# openservo.net
KiCad netlist of a schematic drawn in Altium Designer
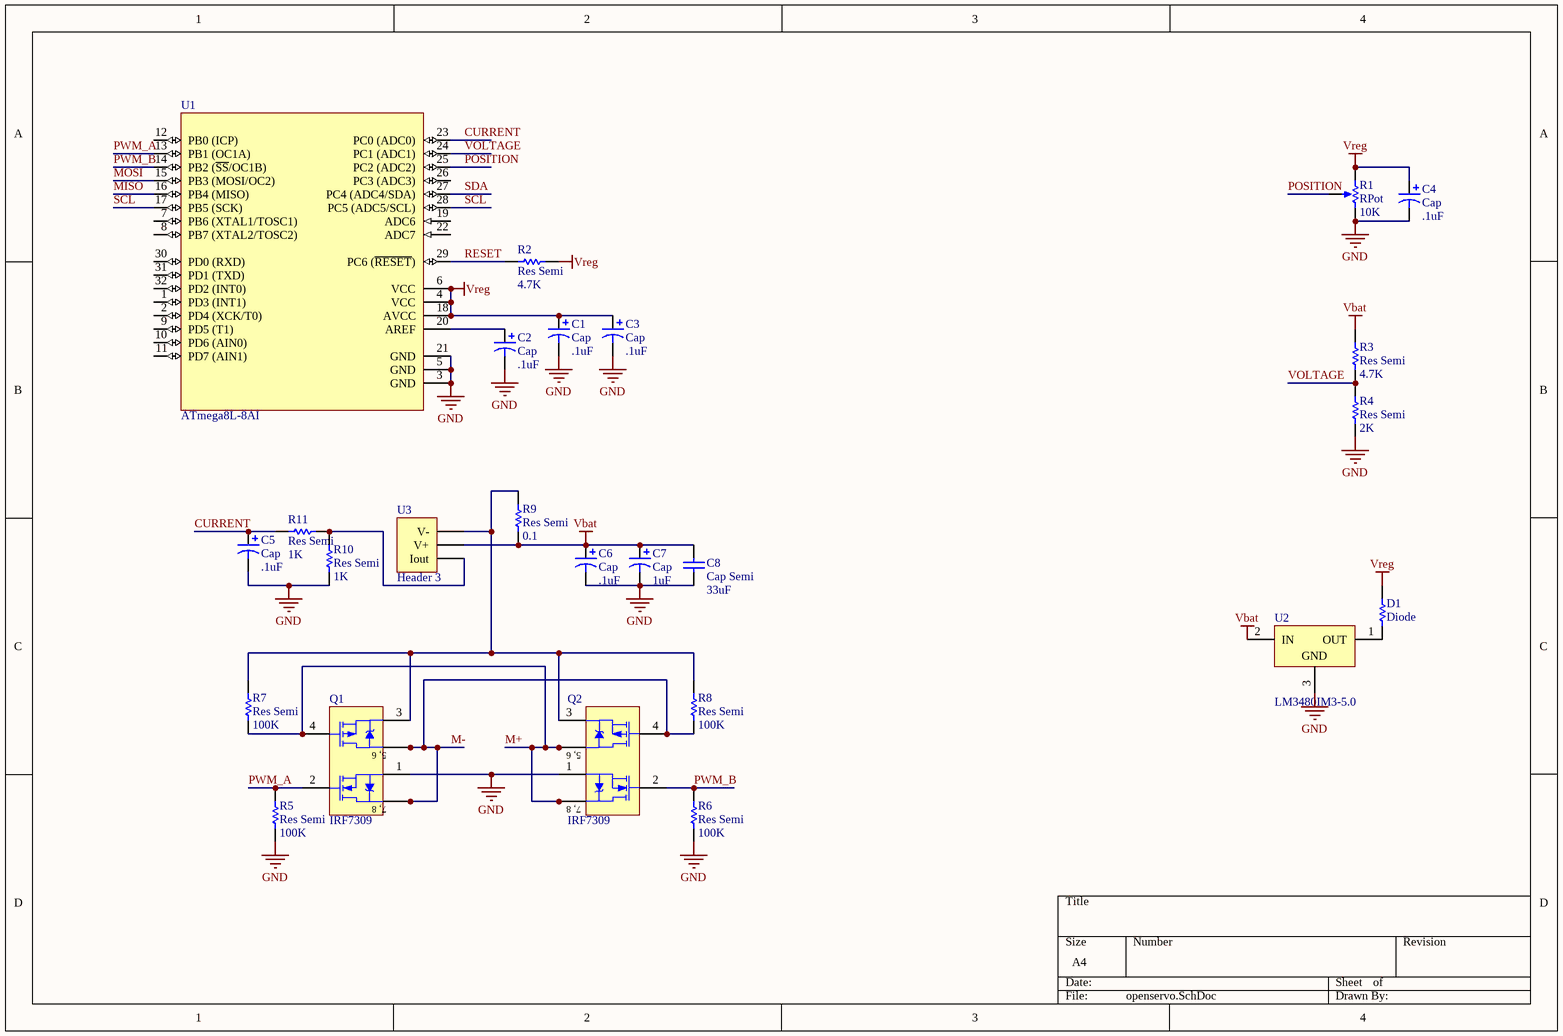
[diagram p0: openservo.SchDoc]

(export (version "E")
  (design (tool "Eeschema 10.0.6"))
  (components
    (comp (ref "C1")
      (value "Cap")
      (footprint "J1-0603")
      (description "Polarized Capacitor (Surface Mount)")
      (fields (field (name "ALTIUM_VALUE") ".1uF") (field (name "PUBLISHER") "Altium Limited"))
      (libsource (lib "Miscellaneous Devices") (part "Cap Semi"))
    )
    (comp (ref "C2")
      (value "Cap")
      (footprint "J1-0603")
      (description "Polarized Capacitor (Surface Mount)")
      (fields (field (name "ALTIUM_VALUE") ".1uF") (field (name "PUBLISHER") "Altium Limited"))
      (libsource (lib "Miscellaneous Devices") (part "Cap Semi"))
    )
    (comp (ref "C3")
      (value "Cap")
      (footprint "J1-0603")
      (description "Polarized Capacitor (Surface Mount)")
      (fields (field (name "ALTIUM_VALUE") ".1uF") (field (name "PUBLISHER") "Altium Limited"))
      (libsource (lib "Miscellaneous Devices") (part "Cap Semi"))
    )
    (comp (ref "C4")
      (value "Cap")
      (footprint "J1-0603")
      (description "Polarized Capacitor (Surface Mount)")
      (fields (field (name "ALTIUM_VALUE") ".1uF") (field (name "PUBLISHER") "Altium Limited"))
      (libsource (lib "Miscellaneous Devices") (part "Cap Semi"))
    )
    (comp (ref "C5")
      (value "Cap")
      (footprint "J1-0603")
      (description "Polarized Capacitor (Surface Mount)")
      (fields (field (name "ALTIUM_VALUE") ".1uF") (field (name "PUBLISHER") "Altium Limited"))
      (libsource (lib "Miscellaneous Devices") (part "Cap Semi"))
    )
    (comp (ref "C6")
      (value "Cap")
      (footprint "J1-0603")
      (description "Polarized Capacitor (Surface Mount)")
      (fields (field (name "ALTIUM_VALUE") ".1uF") (field (name "PUBLISHER") "Altium Limited"))
      (libsource (lib "Miscellaneous Devices") (part "Cap Semi"))
    )
    (comp (ref "C7")
      (value "Cap")
      (footprint "J1-0603")
      (description "Polarized Capacitor (Surface Mount)")
      (fields (field (name "ALTIUM_VALUE") "1uF") (field (name "PUBLISHER") "Altium Limited"))
      (libsource (lib "Miscellaneous Devices") (part "Cap Semi"))
    )
    (comp (ref "C8")
      (value "Cap Semi")
      (footprint "C1210")
      (description "Capacitor (Semiconductor SIM Model)")
      (fields (field (name "ALTIUM_VALUE") "33uF") (field (name "PUBLISHER") "Altium Limited"))
      (libsource (lib "") (part "Cap Semi_1"))
    )
    (comp (ref "D1")
      (value "Diode")
      (footprint "2012[0805]")
      (description "Semiconductor Resistor")
      (fields (field (name "PUBLISHER") "Altium Limited"))
      (libsource (lib "Miscellaneous Devices") (part "Res Semi"))
    )
    (comp (ref "Q1")
      (value "IRF7309")
      (footprint "SO-8_N")
      (description "HEXFET Power MOSFET")
      (fields (field (name "PUBLISHER") "Altium Limited"))
      (libsource (lib "IR Discrete MOSFET - Power") (part "IRF7309"))
    )
    (comp (ref "Q2")
      (value "IRF7309")
      (footprint "SO-8_N")
      (description "HEXFET Power MOSFET")
      (fields (field (name "PUBLISHER") "Altium Limited"))
      (libsource (lib "") (part "IRF7309_1"))
    )
    (comp (ref "R1")
      (value "RPot")
      (footprint "VR5")
      (description "Potentiometer")
      (fields (field (name "ALTIUM_VALUE") "10K") (field (name "PUBLISHER") "Altium Limited"))
      (libsource (lib "Miscellaneous Devices") (part "RPot"))
    )
    (comp (ref "R2")
      (value "Res Semi")
      (footprint "1608[0603]")
      (description "Semiconductor Resistor")
      (fields (field (name "ALTIUM_VALUE") "4.7K") (field (name "PUBLISHER") "Altium Limited"))
      (libsource (lib "Miscellaneous Devices") (part "Res Semi"))
    )
    (comp (ref "R3")
      (value "Res Semi")
      (footprint "1608[0603]")
      (description "Semiconductor Resistor")
      (fields (field (name "ALTIUM_VALUE") "4.7K") (field (name "PUBLISHER") "Altium Limited"))
      (libsource (lib "Miscellaneous Devices") (part "Res Semi"))
    )
    (comp (ref "R4")
      (value "Res Semi")
      (footprint "1608[0603]")
      (description "Semiconductor Resistor")
      (fields (field (name "ALTIUM_VALUE") "2K") (field (name "PUBLISHER") "Altium Limited"))
      (libsource (lib "Miscellaneous Devices") (part "Res Semi"))
    )
    (comp (ref "R5")
      (value "Res Semi")
      (footprint "1608[0603]")
      (description "Semiconductor Resistor")
      (fields (field (name "ALTIUM_VALUE") "100K") (field (name "PUBLISHER") "Altium Limited"))
      (libsource (lib "Miscellaneous Devices") (part "Res Semi"))
    )
    (comp (ref "R6")
      (value "Res Semi")
      (footprint "1608[0603]")
      (description "Semiconductor Resistor")
      (fields (field (name "ALTIUM_VALUE") "100K") (field (name "PUBLISHER") "Altium Limited"))
      (libsource (lib "Miscellaneous Devices") (part "Res Semi"))
    )
    (comp (ref "R7")
      (value "Res Semi")
      (footprint "1608[0603]")
      (description "Semiconductor Resistor")
      (fields (field (name "ALTIUM_VALUE") "100K") (field (name "PUBLISHER") "Altium Limited"))
      (libsource (lib "Miscellaneous Devices") (part "Res Semi"))
    )
    (comp (ref "R8")
      (value "Res Semi")
      (footprint "1608[0603]")
      (description "Semiconductor Resistor")
      (fields (field (name "ALTIUM_VALUE") "100K") (field (name "PUBLISHER") "Altium Limited"))
      (libsource (lib "Miscellaneous Devices") (part "Res Semi"))
    )
    (comp (ref "R9")
      (value "Res Semi")
      (footprint "3216[1206]")
      (description "Semiconductor Resistor")
      (fields (field (name "ALTIUM_VALUE") "0.1") (field (name "PUBLISHER") "Altium Limited"))
      (libsource (lib "Miscellaneous Devices") (part "Res Semi"))
    )
    (comp (ref "R10")
      (value "Res Semi")
      (footprint "1608[0603]")
      (description "Semiconductor Resistor")
      (fields (field (name "ALTIUM_VALUE") "1K") (field (name "PUBLISHER") "Altium Limited"))
      (libsource (lib "Miscellaneous Devices") (part "Res Semi"))
    )
    (comp (ref "R11")
      (value "Res Semi")
      (footprint "1608[0603]")
      (description "Semiconductor Resistor")
      (fields (field (name "ALTIUM_VALUE") "1K") (field (name "PUBLISHER") "Altium Limited"))
      (libsource (lib "Miscellaneous Devices") (part "Res Semi"))
    )
    (comp (ref "U1")
      (value "ATmega8L-8AI")
      (footprint "32A_N")
      (description "8-Bit AVR Microcontroller with 8K Bytes of In-System Programmable Flash Memory")
      (fields (field (name "PUBLISHER") "Altium Limited"))
      (libsource (lib "Atmel Microcontroller 8-Bit AVR") (part "ATmega8L-8AI"))
    )
    (comp (ref "U2")
      (value "LM3480IM3-5.0")
      (footprint "MF03A_N")
      (description "100 mA, SOT-23, Quasi Low-Dropout Linear Voltage Regulator")
      (fields
        (field (name "MANUFACTURER") "National Semiconductor")
        (field (name "DIGIKEYPARTNUMBER") "LM3480IM3-5.0CT-ND")
        (field (name "PUBLISHER") "Altium Limited")
      )
      (libsource (lib "NSC LDO") (part "LM3480IM3-5.0"))
    )
    (comp (ref "U3")
      (value "Header 3")
      (footprint "Philips Discrete BJT - Darlington:SOT23_L")
      (description "Header, 3-Pin")
      (fields (field (name "PUBLISHER") "Altium Limited"))
      (libsource (lib "Miscellaneous Connectors") (part "Header 3"))
    )
  )
  (nets
    (net (code "1") (name "/CURRENT") (class "Default")
      (node (ref "C5") (pin "1") (pinfunction "1_1") (pintype "passive"))
      (node (ref "R11") (pin "2") (pinfunction "2_2") (pintype "passive"))
      (node (ref "U1") (pin "23") (pinfunction "PC0_(ADC0)_23") (pintype "bidirectional"))
    )
    (net (code "2") (name "/M+") (class "Default")
      (node (ref "Q1") (pin "4") (pinfunction "G2_4") (pintype "passive"))
      (node (ref "Q2") (pin "5") (pinfunction "D2_5") (pintype "passive"))
      (node (ref "Q2") (pin "6") (pinfunction "D2_6") (pintype "passive"))
      (node (ref "Q2") (pin "7") (pinfunction "D1_7") (pintype "passive"))
      (node (ref "Q2") (pin "8") (pinfunction "D1_8") (pintype "passive"))
      (node (ref "R7") (pin "1") (pinfunction "1_1") (pintype "passive"))
    )
    (net (code "3") (name "/M-") (class "Default")
      (node (ref "Q1") (pin "5") (pinfunction "D2_5") (pintype "passive"))
      (node (ref "Q1") (pin "6") (pinfunction "D2_6") (pintype "passive"))
      (node (ref "Q1") (pin "7") (pinfunction "D1_7") (pintype "passive"))
      (node (ref "Q1") (pin "8") (pinfunction "D1_8") (pintype "passive"))
      (node (ref "Q2") (pin "4") (pinfunction "G2_4") (pintype "passive"))
      (node (ref "R8") (pin "1") (pinfunction "1_1") (pintype "passive"))
    )
    (net (code "4") (name "/MISO") (class "Default")
      (node (ref "U1") (pin "16") (pinfunction "PB4_(MISO)_16") (pintype "bidirectional"))
    )
    (net (code "5") (name "/MOSI") (class "Default")
      (node (ref "U1") (pin "15") (pinfunction "PB3_(MOSI/OC2)_15") (pintype "bidirectional"))
    )
    (net (code "6") (name "/POSITION") (class "Default")
      (node (ref "R1") (pin "2") (pinfunction "TAP_2") (pintype "passive"))
      (node (ref "U1") (pin "25") (pinfunction "PC2_(ADC2)_25") (pintype "bidirectional"))
    )
    (net (code "7") (name "/PWM_A") (class "Default")
      (node (ref "Q1") (pin "2") (pinfunction "G1_2") (pintype "passive"))
      (node (ref "R5") (pin "2") (pinfunction "2_2") (pintype "passive"))
      (node (ref "U1") (pin "13") (pinfunction "PB1_(OC1A)_13") (pintype "bidirectional"))
    )
    (net (code "8") (name "/PWM_B") (class "Default")
      (node (ref "Q2") (pin "2") (pinfunction "G1_2") (pintype "passive"))
      (node (ref "R6") (pin "2") (pinfunction "2_2") (pintype "passive"))
      (node (ref "U1") (pin "14") (pinfunction "PB2_(~{SS}/OC1B)_14") (pintype "bidirectional"))
    )
    (net (code "9") (name "/RESET") (class "Default")
      (node (ref "R2") (pin "1") (pinfunction "1_1") (pintype "passive"))
      (node (ref "U1") (pin "29") (pinfunction "PC6_(~{RESET})_29") (pintype "bidirectional"))
    )
    (net (code "10") (name "/SCL") (class "Default")
      (node (ref "U1") (pin "17") (pinfunction "PB5_(SCK)_17") (pintype "bidirectional"))
      (node (ref "U1") (pin "28") (pinfunction "PC5_(ADC5/SCL)_28") (pintype "bidirectional"))
    )
    (net (code "11") (name "/SDA") (class "Default")
      (node (ref "U1") (pin "27") (pinfunction "PC4_(ADC4/SDA)_27") (pintype "bidirectional"))
    )
    (net (code "12") (name "/VOLTAGE") (class "Default")
      (node (ref "R3") (pin "1") (pinfunction "1_1") (pintype "passive"))
      (node (ref "R4") (pin "2") (pinfunction "2_2") (pintype "passive"))
      (node (ref "U1") (pin "24") (pinfunction "PC1_(ADC1)_24") (pintype "bidirectional"))
    )
    (net (code "13") (name "GND") (class "Default")
      (node (ref "C1") (pin "2") (pinfunction "2_2") (pintype "passive"))
      (node (ref "C2") (pin "2") (pinfunction "2_2") (pintype "passive"))
      (node (ref "C3") (pin "2") (pinfunction "2_2") (pintype "passive"))
      (node (ref "C4") (pin "2") (pinfunction "2_2") (pintype "passive"))
      (node (ref "C5") (pin "2") (pinfunction "2_2") (pintype "passive"))
      (node (ref "C6") (pin "2") (pinfunction "2_2") (pintype "passive"))
      (node (ref "C7") (pin "2") (pinfunction "2_2") (pintype "passive"))
      (node (ref "C8") (pin "1") (pinfunction "1_1") (pintype "passive"))
      (node (ref "Q1") (pin "1") (pinfunction "S1_1") (pintype "passive"))
      (node (ref "Q2") (pin "1") (pinfunction "S1_1") (pintype "passive"))
      (node (ref "R1") (pin "3") (pinfunction "BOT_3") (pintype "passive"))
      (node (ref "R10") (pin "1") (pinfunction "1_1") (pintype "passive"))
      (node (ref "R4") (pin "1") (pinfunction "1_1") (pintype "passive"))
      (node (ref "R5") (pin "1") (pinfunction "1_1") (pintype "passive"))
      (node (ref "R6") (pin "1") (pinfunction "1_1") (pintype "passive"))
      (node (ref "U1") (pin "21") (pinfunction "GND_21") (pintype "power_in"))
      (node (ref "U1") (pin "3") (pinfunction "GND_3") (pintype "power_in"))
      (node (ref "U1") (pin "5") (pinfunction "GND_5") (pintype "power_in"))
      (node (ref "U2") (pin "3") (pinfunction "GND_3") (pintype "power_in"))
    )
    (net (code "14") (name "Net-(Q1-S2)") (class "Default")
      (node (ref "Q1") (pin "3") (pinfunction "S2_3") (pintype "passive"))
      (node (ref "Q2") (pin "3") (pinfunction "S2_3") (pintype "passive"))
      (node (ref "R7") (pin "2") (pinfunction "2_2") (pintype "passive"))
      (node (ref "R8") (pin "2") (pinfunction "2_2") (pintype "passive"))
      (node (ref "R9") (pin "2") (pinfunction "2_2") (pintype "passive"))
      (node (ref "U3") (pin "1") (pinfunction "V-_1") (pintype "passive"))
    )
    (net (code "15") (name "Net-(U1-AREF)") (class "Default")
      (node (ref "C2") (pin "1") (pinfunction "1_1") (pintype "passive"))
      (node (ref "U1") (pin "20") (pinfunction "AREF_20") (pintype "passive"))
    )
    (net (code "16") (name "Net-(U2-OUT)") (class "Default")
      (node (ref "D1") (pin "1") (pinfunction "1_1") (pintype "passive"))
      (node (ref "U2") (pin "1") (pinfunction "OUT_1") (pintype "power_in"))
    )
    (net (code "17") (name "Net-(U3-Iout)") (class "Default")
      (node (ref "R10") (pin "2") (pinfunction "2_2") (pintype "passive"))
      (node (ref "R11") (pin "1") (pinfunction "1_1") (pintype "passive"))
      (node (ref "U3") (pin "3") (pinfunction "Iout_3") (pintype "passive"))
    )
    (net (code "18") (name "Vbat") (class "Default")
      (node (ref "C6") (pin "1") (pinfunction "1_1") (pintype "passive"))
      (node (ref "C7") (pin "1") (pinfunction "1_1") (pintype "passive"))
      (node (ref "C8") (pin "2") (pinfunction "2_2") (pintype "passive"))
      (node (ref "R3") (pin "2") (pinfunction "2_2") (pintype "passive"))
      (node (ref "R9") (pin "1") (pinfunction "1_1") (pintype "passive"))
      (node (ref "U2") (pin "2") (pinfunction "IN_2") (pintype "power_in"))
      (node (ref "U3") (pin "2") (pinfunction "V+_2") (pintype "passive"))
    )
    (net (code "19") (name "Vreg") (class "Default")
      (node (ref "C1") (pin "1") (pinfunction "1_1") (pintype "passive"))
      (node (ref "C3") (pin "1") (pinfunction "1_1") (pintype "passive"))
      (node (ref "C4") (pin "1") (pinfunction "1_1") (pintype "passive"))
      (node (ref "D1") (pin "2") (pinfunction "2_2") (pintype "passive"))
      (node (ref "R1") (pin "1") (pinfunction "TOP_1") (pintype "passive"))
      (node (ref "R2") (pin "2") (pinfunction "2_2") (pintype "passive"))
      (node (ref "U1") (pin "18") (pinfunction "AVCC_18") (pintype "power_in"))
      (node (ref "U1") (pin "4") (pinfunction "VCC_4") (pintype "power_in"))
      (node (ref "U1") (pin "6") (pinfunction "VCC_6") (pintype "power_in"))
    )
    (net (code "20") (name "unconnected-(U1-ADC6-Pad19)") (class "Default")
      (node (ref "U1") (pin "19") (pinfunction "ADC6_19") (pintype "input"))
    )
    (net (code "21") (name "unconnected-(U1-ADC7-Pad22)") (class "Default")
      (node (ref "U1") (pin "22") (pinfunction "ADC7_22") (pintype "input"))
    )
    (net (code "22") (name "unconnected-(U1-PB0_(ICP)-Pad12)") (class "Default")
      (node (ref "U1") (pin "12") (pinfunction "PB0_(ICP)_12") (pintype "bidirectional"))
    )
    (net (code "23") (name "unconnected-(U1-PB6_(XTAL1{slash}TOSC1)-Pad7)") (class "Default")
      (node (ref "U1") (pin "7") (pinfunction "PB6_(XTAL1/TOSC1)_7") (pintype "bidirectional"))
    )
    (net (code "24") (name "unconnected-(U1-PB7_(XTAL2{slash}TOSC2)-Pad8)") (class "Default")
      (node (ref "U1") (pin "8") (pinfunction "PB7_(XTAL2/TOSC2)_8") (pintype "bidirectional"))
    )
    (net (code "25") (name "unconnected-(U1-PC3_(ADC3)-Pad26)") (class "Default")
      (node (ref "U1") (pin "26") (pinfunction "PC3_(ADC3)_26") (pintype "bidirectional"))
    )
    (net (code "26") (name "unconnected-(U1-PD0_(RXD)-Pad30)") (class "Default")
      (node (ref "U1") (pin "30") (pinfunction "PD0_(RXD)_30") (pintype "bidirectional"))
    )
    (net (code "27") (name "unconnected-(U1-PD1_(TXD)-Pad31)") (class "Default")
      (node (ref "U1") (pin "31") (pinfunction "PD1_(TXD)_31") (pintype "bidirectional"))
    )
    (net (code "28") (name "unconnected-(U1-PD2_(INT0)-Pad32)") (class "Default")
      (node (ref "U1") (pin "32") (pinfunction "PD2_(INT0)_32") (pintype "bidirectional"))
    )
    (net (code "29") (name "unconnected-(U1-PD3_(INT1)-Pad1)") (class "Default")
      (node (ref "U1") (pin "1") (pinfunction "PD3_(INT1)_1") (pintype "bidirectional"))
    )
    (net (code "30") (name "unconnected-(U1-PD4_(XCK{slash}T0)-Pad2)") (class "Default")
      (node (ref "U1") (pin "2") (pinfunction "PD4_(XCK/T0)_2") (pintype "bidirectional"))
    )
    (net (code "31") (name "unconnected-(U1-PD5_(T1)-Pad9)") (class "Default")
      (node (ref "U1") (pin "9") (pinfunction "PD5_(T1)_9") (pintype "bidirectional"))
    )
    (net (code "32") (name "unconnected-(U1-PD6_(AIN0)-Pad10)") (class "Default")
      (node (ref "U1") (pin "10") (pinfunction "PD6_(AIN0)_10") (pintype "bidirectional"))
    )
    (net (code "33") (name "unconnected-(U1-PD7_(AIN1)-Pad11)") (class "Default")
      (node (ref "U1") (pin "11") (pinfunction "PD7_(AIN1)_11") (pintype "bidirectional"))
    )
  )
)
